# Grove_-_GPS_v1_1.net
KiCad netlist of a schematic drawn in EAGLE
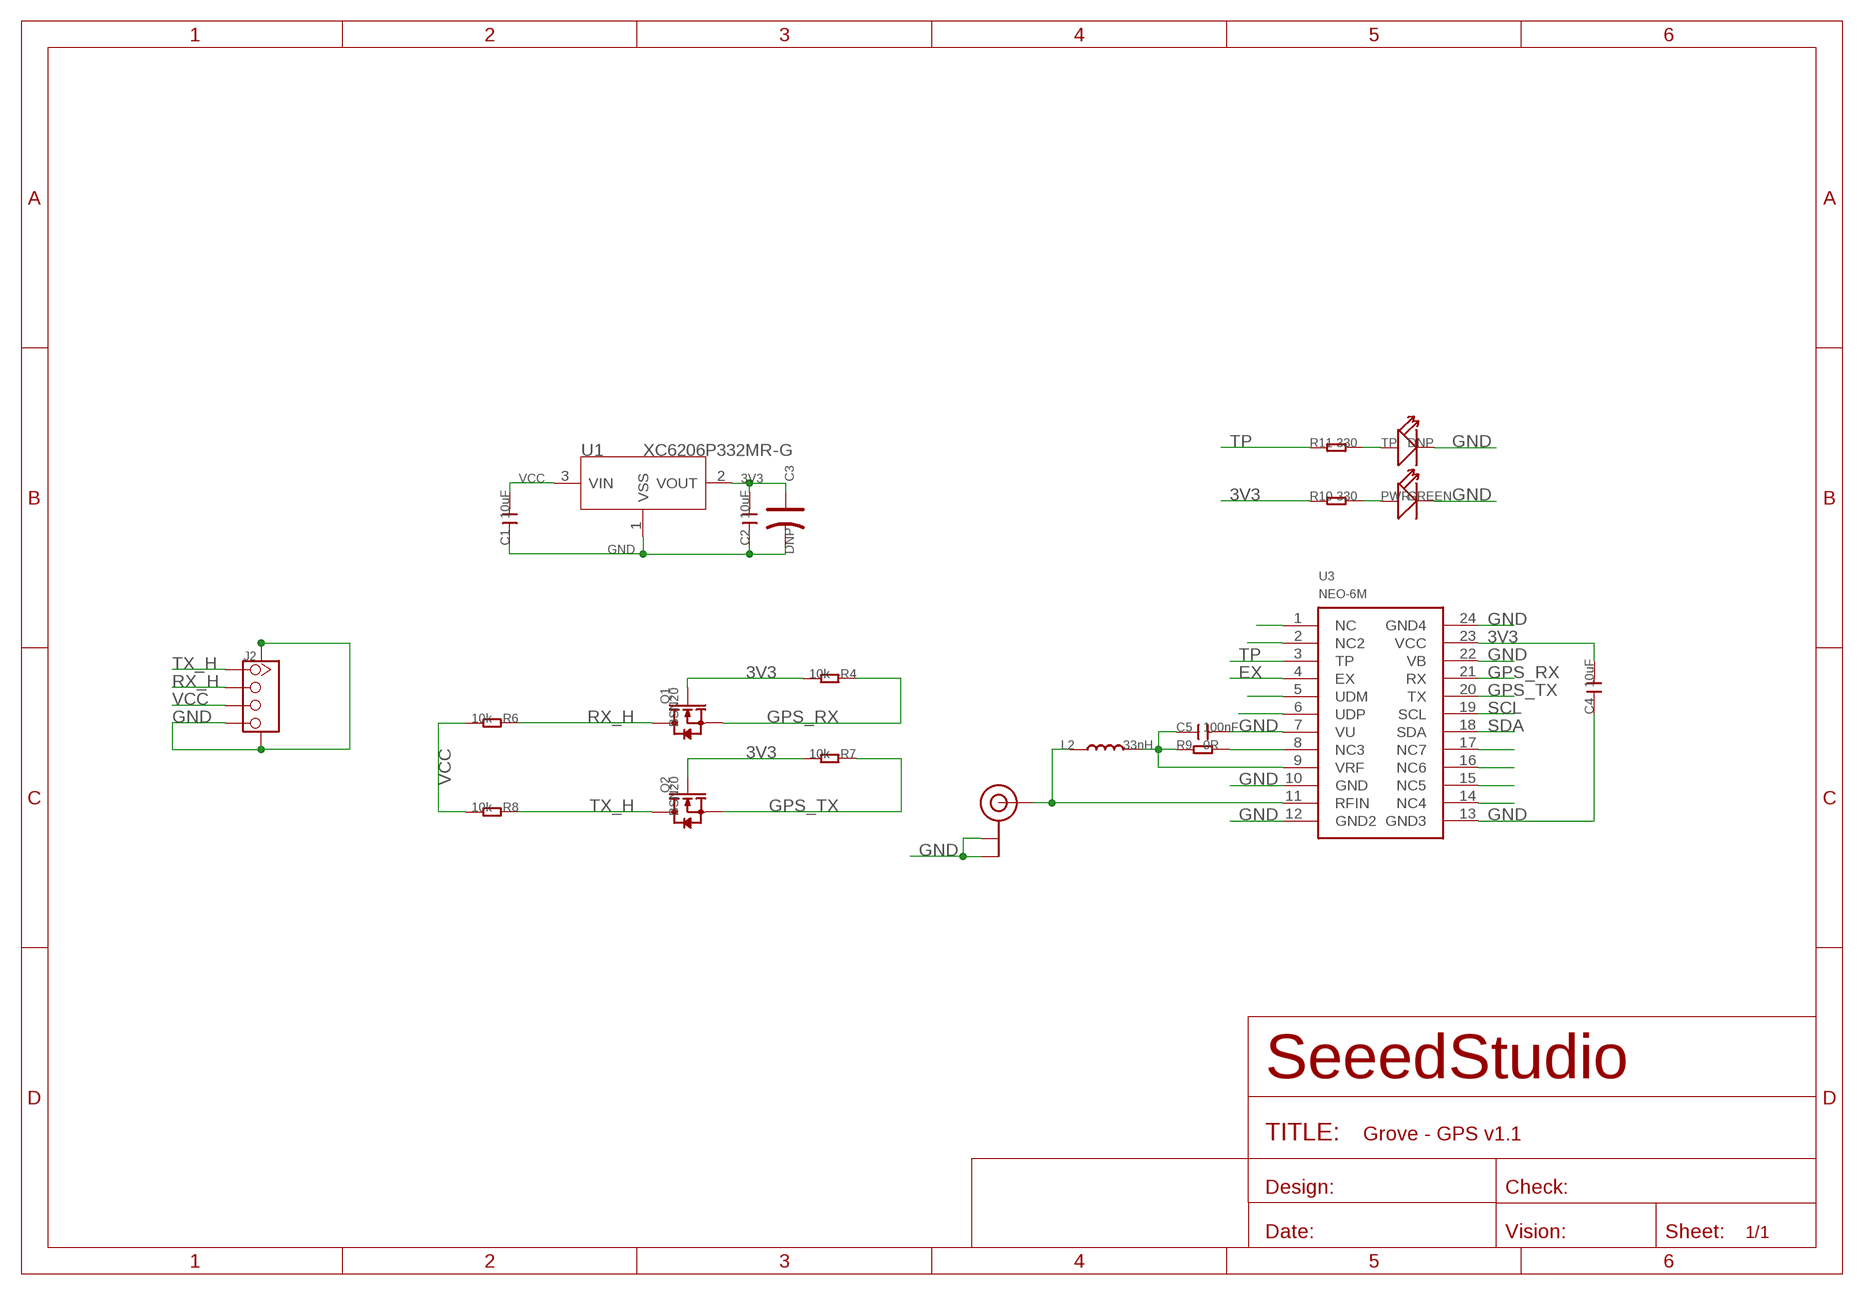
[diagram p0: schematic, sheet 1]

(export (version "E")
  (design (tool "Eeschema 10.0.6"))
  (components
    (comp (ref "C1")
      (value "10uF")
      (footprint "eagle-import:C0805")
      (libsource (lib "eagle-import") (part "C-0805"))
    )
    (comp (ref "C2")
      (value "10uF")
      (footprint "eagle-import:C0805")
      (libsource (lib "eagle-import") (part "C-0805"))
    )
    (comp (ref "C3")
      (value "DNP")
      (footprint "eagle-import:AVX-A")
      (libsource (lib "eagle-import") (part "CAP-AVX-A"))
    )
    (comp (ref "C4")
      (value "10uF")
      (footprint "eagle-import:C0805")
      (libsource (lib "eagle-import") (part "C-0805"))
    )
    (comp (ref "C5")
      (value "100nF")
      (footprint "eagle-import:C0603")
      (libsource (lib "eagle-import") (part "C-0603"))
    )
    (comp (ref "J2")
      (value "TWIG-4P-2.0-SMD-FEMALE-REINFORCE'DD'")
      (footprint "eagle-import:4P-SMD-2.0")
      (libsource (lib "eagle-import") (part "TWIG-4P-2.0-SMD-FEMALE-REINFORCE'DD'"))
    )
    (comp (ref "L2")
      (value "33nH")
      (footprint "eagle-import:L0603")
      (libsource (lib "eagle-import") (part "L'0603'"))
    )
    (comp (ref "PWR")
      (value "GREEN")
      (footprint "eagle-import:LED-0603")
      (libsource (lib "eagle-import") (part "LED'0603'"))
    )
    (comp (ref "Q1")
      (value "BSN20")
      (footprint "eagle-import:SOT23")
      (libsource (lib "eagle-import") (part "MOSFET-N'SOT23'"))
    )
    (comp (ref "Q2")
      (value "BSN20")
      (footprint "eagle-import:SOT23")
      (libsource (lib "eagle-import") (part "MOSFET-N'SOT23'"))
    )
    (comp (ref "R4")
      (value "10k")
      (footprint "eagle-import:R0603")
      (libsource (lib "eagle-import") (part "R-0603"))
    )
    (comp (ref "R6")
      (value "10k")
      (footprint "eagle-import:R0603")
      (libsource (lib "eagle-import") (part "R-0603"))
    )
    (comp (ref "R7")
      (value "10k")
      (footprint "eagle-import:R0603")
      (libsource (lib "eagle-import") (part "R-0603"))
    )
    (comp (ref "R8")
      (value "10k")
      (footprint "eagle-import:R0603")
      (libsource (lib "eagle-import") (part "R-0603"))
    )
    (comp (ref "R9")
      (value "0R")
      (footprint "eagle-import:R0603")
      (libsource (lib "eagle-import") (part "R-0603"))
    )
    (comp (ref "R10")
      (value "330")
      (footprint "eagle-import:R0603")
      (libsource (lib "eagle-import") (part "R-0603"))
    )
    (comp (ref "R11")
      (value "330")
      (footprint "eagle-import:R0603")
      (libsource (lib "eagle-import") (part "R-0603"))
    )
    (comp (ref "TP")
      (value "DNP")
      (footprint "eagle-import:LED-0603")
      (libsource (lib "eagle-import") (part "LED'0603'"))
    )
    (comp (ref "U1")
      (value "XC6206P332MR-G")
      (footprint "eagle-import:SOT23")
      (libsource (lib "eagle-import") (part "XC6206MR"))
    )
    (comp (ref "U3")
      (value "NEO-6M")
      (footprint "eagle-import:28P-1.1-16.0X12.2")
      (libsource (lib "eagle-import") (part "NEO-6M"))
    )
    (comp (ref "U4")
      (value "U.FL")
      (footprint "eagle-import:U.FL")
      (libsource (lib "eagle-import") (part "U.FL"))
    )
  )
  (nets
    (net (code "1") (name "/3V3") (class "Default")
      (node (ref "C2") (pin "2") (pinfunction "2_2") (pintype "passive"))
      (node (ref "C3") (pin "+") (pinfunction "+_+") (pintype "passive"))
      (node (ref "C4") (pin "2") (pinfunction "2_2") (pintype "passive"))
      (node (ref "Q1") (pin "1") (pinfunction "G_1") (pintype "passive"))
      (node (ref "Q2") (pin "1") (pinfunction "G_1") (pintype "passive"))
      (node (ref "R10") (pin "1") (pinfunction "1_1") (pintype "passive"))
      (node (ref "R4") (pin "2") (pinfunction "2_2") (pintype "passive"))
      (node (ref "R7") (pin "2") (pinfunction "2_2") (pintype "passive"))
      (node (ref "U1") (pin "2") (pinfunction "VOUT_2") (pintype "output"))
      (node (ref "U3") (pin "23") (pinfunction "VCC_23") (pintype "bidirectional"))
    )
    (net (code "2") (name "/EX") (class "Default")
      (node (ref "U3") (pin "4") (pinfunction "EX_4") (pintype "bidirectional"))
    )
    (net (code "3") (name "/GND") (class "Default")
      (node (ref "C1") (pin "1") (pinfunction "1_1") (pintype "passive"))
      (node (ref "C2") (pin "1") (pinfunction "1_1") (pintype "passive"))
      (node (ref "C3") (pin "-") (pinfunction "-_-") (pintype "passive"))
      (node (ref "C4") (pin "1") (pinfunction "1_1") (pintype "passive"))
      (node (ref "C5") (pin "2") (pinfunction "2_2") (pintype "passive"))
      (node (ref "J2") (pin "4") (pinfunction "4_4") (pintype "bidirectional"))
      (node (ref "J2") (pin "SS1") (pinfunction "SS1_SS1") (pintype "bidirectional"))
      (node (ref "J2") (pin "SS2") (pinfunction "SS2_SS2") (pintype "bidirectional"))
      (node (ref "PWR") (pin "-") (pinfunction "-_-") (pintype "passive"))
      (node (ref "TP") (pin "-") (pinfunction "-_-") (pintype "passive"))
      (node (ref "U1") (pin "1") (pinfunction "VSS_1") (pintype "power_in"))
      (node (ref "U3") (pin "10") (pinfunction "GND_10") (pintype "bidirectional"))
      (node (ref "U3") (pin "12") (pinfunction "GND2_12") (pintype "bidirectional"))
      (node (ref "U3") (pin "13") (pinfunction "GND3_13") (pintype "bidirectional"))
      (node (ref "U3") (pin "22") (pinfunction "VB_22") (pintype "bidirectional"))
      (node (ref "U3") (pin "24") (pinfunction "GND4_24") (pintype "bidirectional"))
      (node (ref "U3") (pin "7") (pinfunction "VU_7") (pintype "bidirectional"))
      (node (ref "U4") (pin "P$1") (pinfunction "GND_P$1") (pintype "bidirectional"))
      (node (ref "U4") (pin "P$2") (pinfunction "GND_P$2") (pintype "bidirectional"))
    )
    (net (code "4") (name "/GPS_RX") (class "Default")
      (node (ref "Q1") (pin "2") (pinfunction "S_2") (pintype "passive"))
      (node (ref "R4") (pin "1") (pinfunction "1_1") (pintype "passive"))
      (node (ref "U3") (pin "21") (pinfunction "RX_21") (pintype "bidirectional"))
    )
    (net (code "5") (name "/GPS_TX") (class "Default")
      (node (ref "Q2") (pin "2") (pinfunction "S_2") (pintype "passive"))
      (node (ref "R7") (pin "1") (pinfunction "1_1") (pintype "passive"))
      (node (ref "U3") (pin "20") (pinfunction "TX_20") (pintype "bidirectional"))
    )
    (net (code "6") (name "/RX_H") (class "Default")
      (node (ref "J2") (pin "2") (pinfunction "2_2") (pintype "bidirectional"))
      (node (ref "Q1") (pin "3") (pinfunction "D_3") (pintype "passive"))
      (node (ref "R6") (pin "1") (pinfunction "1_1") (pintype "passive"))
    )
    (net (code "7") (name "/SCL") (class "Default")
      (node (ref "U3") (pin "19") (pinfunction "SCL_19") (pintype "bidirectional"))
    )
    (net (code "8") (name "/SDA") (class "Default")
      (node (ref "U3") (pin "18") (pinfunction "SDA_18") (pintype "bidirectional"))
    )
    (net (code "9") (name "/TP") (class "Default")
      (node (ref "R11") (pin "1") (pinfunction "1_1") (pintype "passive"))
      (node (ref "U3") (pin "3") (pinfunction "TP_3") (pintype "bidirectional"))
    )
    (net (code "10") (name "/TX_H") (class "Default")
      (node (ref "J2") (pin "1") (pinfunction "1_1") (pintype "bidirectional"))
      (node (ref "Q2") (pin "3") (pinfunction "D_3") (pintype "passive"))
      (node (ref "R8") (pin "1") (pinfunction "1_1") (pintype "passive"))
    )
    (net (code "11") (name "/VCC") (class "Default")
      (node (ref "C1") (pin "2") (pinfunction "2_2") (pintype "passive"))
      (node (ref "J2") (pin "3") (pinfunction "3_3") (pintype "bidirectional"))
      (node (ref "R6") (pin "2") (pinfunction "2_2") (pintype "passive"))
      (node (ref "R8") (pin "2") (pinfunction "2_2") (pintype "passive"))
      (node (ref "U1") (pin "3") (pinfunction "VIN_3") (pintype "input"))
    )
    (net (code "12") (name "Net-(PWR-Pad+)") (class "Default")
      (node (ref "PWR") (pin "+") (pinfunction "+_+") (pintype "passive"))
      (node (ref "R10") (pin "2") (pinfunction "2_2") (pintype "passive"))
    )
    (net (code "13") (name "Net-(R11-Pad2)") (class "Default")
      (node (ref "R11") (pin "2") (pinfunction "2_2") (pintype "passive"))
      (node (ref "TP") (pin "+") (pinfunction "+_+") (pintype "passive"))
    )
    (net (code "14") (name "Net-(U3-NC3)") (class "Default")
      (node (ref "R9") (pin "2") (pinfunction "2_2") (pintype "passive"))
      (node (ref "U3") (pin "8") (pinfunction "NC3_8") (pintype "bidirectional"))
    )
    (net (code "15") (name "Net-(U3-RFIN)") (class "Default")
      (node (ref "L2") (pin "1") (pinfunction "1_1") (pintype "passive"))
      (node (ref "U3") (pin "11") (pinfunction "RFIN_11") (pintype "bidirectional"))
      (node (ref "U4") (pin "P$3") (pinfunction "SIGNAL_P$3") (pintype "bidirectional"))
    )
    (net (code "16") (name "Net-(U3-VRF)") (class "Default")
      (node (ref "C5") (pin "1") (pinfunction "1_1") (pintype "passive"))
      (node (ref "L2") (pin "2") (pinfunction "2_2") (pintype "passive"))
      (node (ref "R9") (pin "1") (pinfunction "1_1") (pintype "passive"))
      (node (ref "U3") (pin "9") (pinfunction "VRF_9") (pintype "bidirectional"))
    )
    (net (code "17") (name "unconnected-(U3-NC-Pad1)") (class "Default")
      (node (ref "U3") (pin "1") (pinfunction "NC_1") (pintype "bidirectional"))
    )
    (net (code "18") (name "unconnected-(U3-NC2-Pad2)") (class "Default")
      (node (ref "U3") (pin "2") (pinfunction "NC2_2") (pintype "bidirectional"))
    )
    (net (code "19") (name "unconnected-(U3-NC4-Pad14)") (class "Default")
      (node (ref "U3") (pin "14") (pinfunction "NC4_14") (pintype "bidirectional"))
    )
    (net (code "20") (name "unconnected-(U3-NC5-Pad15)") (class "Default")
      (node (ref "U3") (pin "15") (pinfunction "NC5_15") (pintype "bidirectional"))
    )
    (net (code "21") (name "unconnected-(U3-NC6-Pad16)") (class "Default")
      (node (ref "U3") (pin "16") (pinfunction "NC6_16") (pintype "bidirectional"))
    )
    (net (code "22") (name "unconnected-(U3-NC7-Pad17)") (class "Default")
      (node (ref "U3") (pin "17") (pinfunction "NC7_17") (pintype "bidirectional"))
    )
    (net (code "23") (name "unconnected-(U3-UDM-Pad5)") (class "Default")
      (node (ref "U3") (pin "5") (pinfunction "UDM_5") (pintype "bidirectional"))
    )
    (net (code "24") (name "unconnected-(U3-UDP-Pad6)") (class "Default")
      (node (ref "U3") (pin "6") (pinfunction "UDP_6") (pintype "bidirectional"))
    )
  )
)
